# Sche1.net
KiCad netlist of a schematic drawn in EAGLE
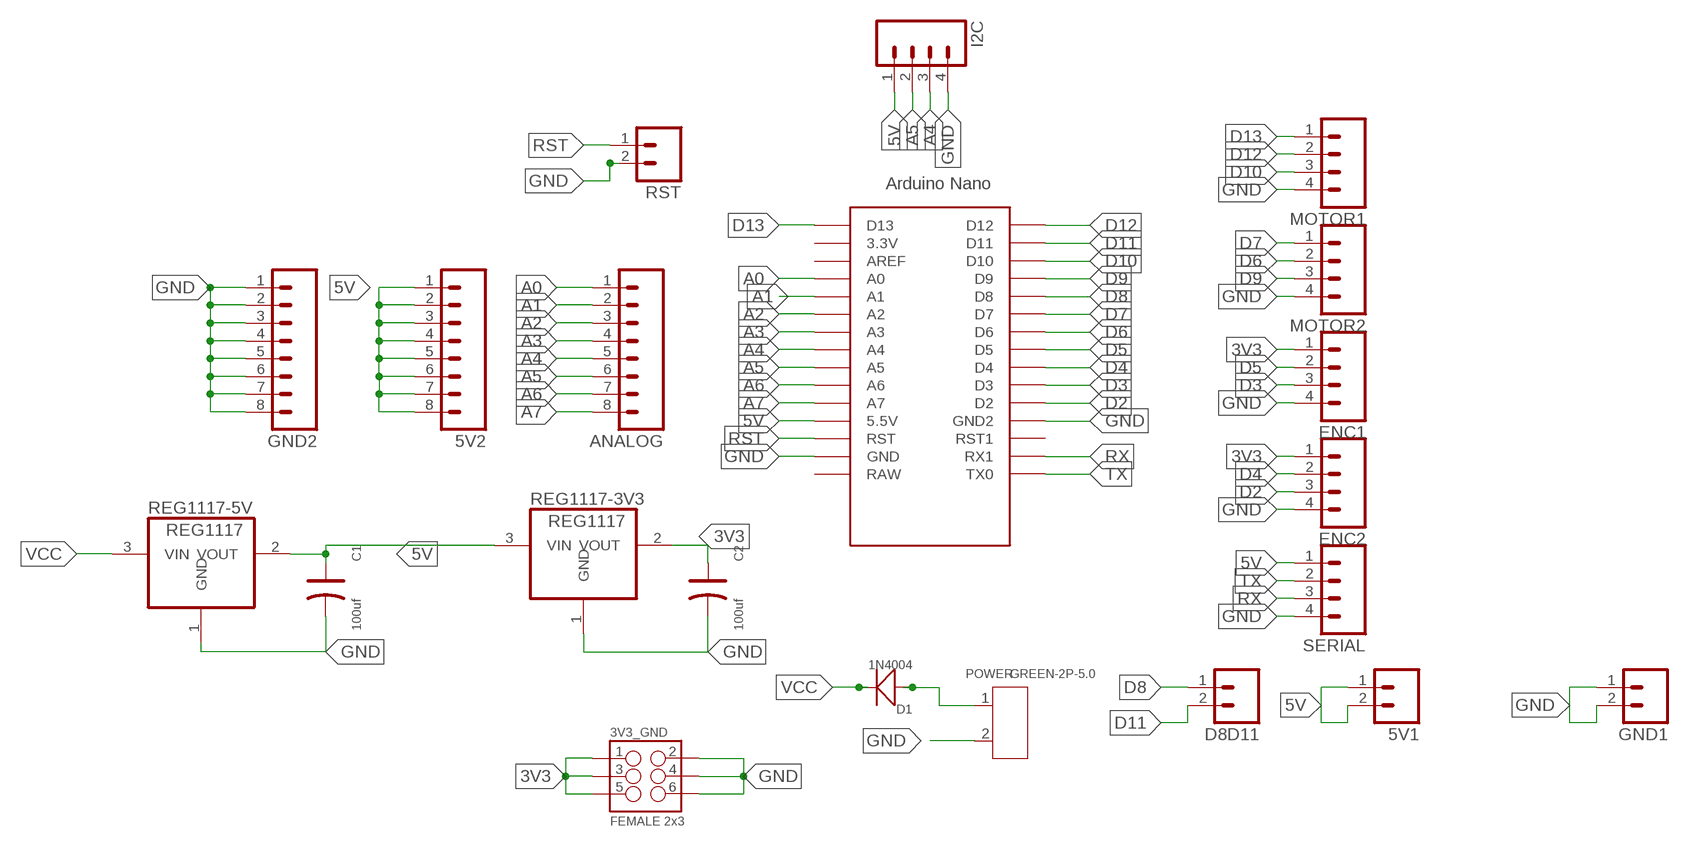
[diagram p0: schematic, sheet 1]

(export (version "E")
  (design (tool "Eeschema 10.0.6"))
  (components
    (comp (ref "3V3_GND")
      (value "FEMALE 2x3")
      (footprint "eagle-import:2X3")
      (libsource (lib "eagle-import") (part "M03X2FEMALE"))
    )
    (comp (ref "5V1")
      (value "M02PTH")
      (footprint "eagle-import:1X02")
      (libsource (lib "eagle-import") (part "M02PTH"))
    )
    (comp (ref "5V2")
      (value "M08SILK_FEMALE_PTH")
      (footprint "eagle-import:1X08")
      (libsource (lib "eagle-import") (part "M08SILK_FEMALE_PTH"))
    )
    (comp (ref "ANALOG")
      (value "M08SILK_FEMALE_PTH")
      (footprint "eagle-import:1X08")
      (libsource (lib "eagle-import") (part "M08SILK_FEMALE_PTH"))
    )
    (comp (ref "C1")
      (value "100uf")
      (footprint "eagle-import:PC-D5.3MM")
      (fields (field (name "MPN") "KS 100uF/16V"))
      (libsource (lib "eagle-import") (part "DIP-ALUMINUM-100UF-16V(D5-H7MM)"))
    )
    (comp (ref "C2")
      (value "100uf")
      (footprint "eagle-import:PC-D5.3MM")
      (fields (field (name "MPN") "KS 100uF/16V"))
      (libsource (lib "eagle-import") (part "DIP-ALUMINUM-100UF-16V(D5-H7MM)"))
    )
    (comp (ref "D1")
      (value "1N4004")
      (footprint "eagle-import:DO-41")
      (libsource (lib "eagle-import") (part "DIP-DIODE-400V-1A(DO-41)"))
    )
    (comp (ref "D8D11")
      (value "M02PTH")
      (footprint "eagle-import:1X02")
      (libsource (lib "eagle-import") (part "M02PTH"))
    )
    (comp (ref "ENC1")
      (value "M04PTH")
      (footprint "eagle-import:1X04")
      (libsource (lib "eagle-import") (part "M04PTH"))
    )
    (comp (ref "ENC2")
      (value "M04PTH")
      (footprint "eagle-import:1X04")
      (libsource (lib "eagle-import") (part "M04PTH"))
    )
    (comp (ref "GND1")
      (value "M02PTH")
      (footprint "eagle-import:1X02")
      (libsource (lib "eagle-import") (part "M02PTH"))
    )
    (comp (ref "GND2")
      (value "M08SILK_FEMALE_PTH")
      (footprint "eagle-import:1X08")
      (libsource (lib "eagle-import") (part "M08SILK_FEMALE_PTH"))
    )
    (comp (ref "I2C")
      (value "M04PTH")
      (footprint "eagle-import:1X04")
      (libsource (lib "eagle-import") (part "M04PTH"))
    )
    (comp (ref "MOTOR1")
      (value "M04PTH")
      (footprint "eagle-import:1X04")
      (libsource (lib "eagle-import") (part "M04PTH"))
    )
    (comp (ref "MOTOR2")
      (value "M04PTH")
      (footprint "eagle-import:1X04")
      (libsource (lib "eagle-import") (part "M04PTH"))
    )
    (comp (ref "POWER")
      (value "GREEN-2P-5.0")
      (footprint "eagle-import:H2-5.0-10.5X8.0MM")
      (libsource (lib "eagle-import") (part "SCREW-TERMINAL-GREEN(2P-5.0)"))
    )
    (comp (ref "REG1117-3V3")
      (value "REG1117")
      (footprint "eagle-import:SOT223")
      (libsource (lib "eagle-import") (part "REG1117"))
    )
    (comp (ref "REG1117-5V")
      (value "REG1117")
      (footprint "eagle-import:SOT223")
      (libsource (lib "eagle-import") (part "REG1117"))
    )
    (comp (ref "RST")
      (value "M02PTH")
      (footprint "eagle-import:1X02")
      (libsource (lib "eagle-import") (part "M02PTH"))
    )
    (comp (ref "SERIAL")
      (value "M04PTH")
      (footprint "eagle-import:1X04")
      (libsource (lib "eagle-import") (part "M04PTH"))
    )
    (comp (ref "U$1")
      (value "NANO")
      (footprint "eagle-import:NANO")
      (libsource (lib "eagle-import") (part "NANO"))
    )
  )
  (nets
    (net (code "1") (name "3V3") (class "Default")
      (node (ref "3V3_GND") (pin "1") (pinfunction "1_1") (pintype "bidirectional"))
      (node (ref "3V3_GND") (pin "3") (pinfunction "3_3") (pintype "bidirectional"))
      (node (ref "3V3_GND") (pin "5") (pinfunction "5_5") (pintype "bidirectional"))
      (node (ref "C2") (pin "+") (pinfunction "+_+") (pintype "passive"))
      (node (ref "ENC1") (pin "1") (pinfunction "1_1") (pintype "passive"))
      (node (ref "ENC2") (pin "1") (pinfunction "1_1") (pintype "passive"))
      (node (ref "REG1117-3V3") (pin "2") (pinfunction "VOUT_2") (pintype "output"))
    )
    (net (code "2") (name "5V") (class "Default")
      (node (ref "5V1") (pin "1") (pinfunction "1_1") (pintype "passive"))
      (node (ref "5V1") (pin "2") (pinfunction "2_2") (pintype "passive"))
      (node (ref "5V2") (pin "1") (pinfunction "1_1") (pintype "passive"))
      (node (ref "5V2") (pin "2") (pinfunction "2_2") (pintype "passive"))
      (node (ref "5V2") (pin "3") (pinfunction "3_3") (pintype "passive"))
      (node (ref "5V2") (pin "4") (pinfunction "4_4") (pintype "passive"))
      (node (ref "5V2") (pin "5") (pinfunction "5_5") (pintype "passive"))
      (node (ref "5V2") (pin "6") (pinfunction "6_6") (pintype "passive"))
      (node (ref "5V2") (pin "7") (pinfunction "7_7") (pintype "passive"))
      (node (ref "5V2") (pin "8") (pinfunction "8_8") (pintype "passive"))
      (node (ref "C1") (pin "+") (pinfunction "+_+") (pintype "passive"))
      (node (ref "I2C") (pin "1") (pinfunction "1_1") (pintype "passive"))
      (node (ref "REG1117-3V3") (pin "3") (pinfunction "VIN_3") (pintype "input"))
      (node (ref "REG1117-5V") (pin "2") (pinfunction "VOUT_2") (pintype "output"))
      (node (ref "SERIAL") (pin "1") (pinfunction "1_1") (pintype "passive"))
      (node (ref "U$1") (pin "5V") (pinfunction "5.5V_5V") (pintype "bidirectional"))
    )
    (net (code "3") (name "A0") (class "Default")
      (node (ref "ANALOG") (pin "1") (pinfunction "1_1") (pintype "passive"))
      (node (ref "U$1") (pin "A0") (pinfunction "A0_A0") (pintype "bidirectional"))
    )
    (net (code "4") (name "A1") (class "Default")
      (node (ref "ANALOG") (pin "2") (pinfunction "2_2") (pintype "passive"))
      (node (ref "U$1") (pin "A1") (pinfunction "A1_A1") (pintype "bidirectional"))
    )
    (net (code "5") (name "A2") (class "Default")
      (node (ref "ANALOG") (pin "3") (pinfunction "3_3") (pintype "passive"))
      (node (ref "U$1") (pin "A2") (pinfunction "A2_A2") (pintype "bidirectional"))
    )
    (net (code "6") (name "A3") (class "Default")
      (node (ref "ANALOG") (pin "4") (pinfunction "4_4") (pintype "passive"))
      (node (ref "U$1") (pin "A3") (pinfunction "A3_A3") (pintype "bidirectional"))
    )
    (net (code "7") (name "A4") (class "Default")
      (node (ref "ANALOG") (pin "5") (pinfunction "5_5") (pintype "passive"))
      (node (ref "I2C") (pin "3") (pinfunction "3_3") (pintype "passive"))
      (node (ref "U$1") (pin "A4") (pinfunction "A4_A4") (pintype "bidirectional"))
    )
    (net (code "8") (name "A5") (class "Default")
      (node (ref "ANALOG") (pin "6") (pinfunction "6_6") (pintype "passive"))
      (node (ref "I2C") (pin "2") (pinfunction "2_2") (pintype "passive"))
      (node (ref "U$1") (pin "A5") (pinfunction "A5_A5") (pintype "bidirectional"))
    )
    (net (code "9") (name "A6") (class "Default")
      (node (ref "ANALOG") (pin "7") (pinfunction "7_7") (pintype "passive"))
      (node (ref "U$1") (pin "A6") (pinfunction "A6_A6") (pintype "bidirectional"))
    )
    (net (code "10") (name "A7") (class "Default")
      (node (ref "ANALOG") (pin "8") (pinfunction "8_8") (pintype "passive"))
      (node (ref "U$1") (pin "A7") (pinfunction "A7_A7") (pintype "bidirectional"))
    )
    (net (code "11") (name "D2") (class "Default")
      (node (ref "ENC2") (pin "3") (pinfunction "3_3") (pintype "passive"))
      (node (ref "U$1") (pin "D2") (pinfunction "D2_D2") (pintype "bidirectional"))
    )
    (net (code "12") (name "D3") (class "Default")
      (node (ref "ENC1") (pin "3") (pinfunction "3_3") (pintype "passive"))
      (node (ref "U$1") (pin "D3") (pinfunction "D3_D3") (pintype "bidirectional"))
    )
    (net (code "13") (name "D4") (class "Default")
      (node (ref "ENC2") (pin "2") (pinfunction "2_2") (pintype "passive"))
      (node (ref "U$1") (pin "D4") (pinfunction "D4_D4") (pintype "bidirectional"))
    )
    (net (code "14") (name "D5") (class "Default")
      (node (ref "ENC1") (pin "2") (pinfunction "2_2") (pintype "passive"))
      (node (ref "U$1") (pin "D5") (pinfunction "D5_D5") (pintype "bidirectional"))
    )
    (net (code "15") (name "D6") (class "Default")
      (node (ref "MOTOR2") (pin "2") (pinfunction "2_2") (pintype "passive"))
      (node (ref "U$1") (pin "D6") (pinfunction "D6_D6") (pintype "bidirectional"))
    )
    (net (code "16") (name "D7") (class "Default")
      (node (ref "MOTOR2") (pin "1") (pinfunction "1_1") (pintype "passive"))
      (node (ref "U$1") (pin "D7") (pinfunction "D7_D7") (pintype "bidirectional"))
    )
    (net (code "17") (name "D8") (class "Default")
      (node (ref "D8D11") (pin "1") (pinfunction "1_1") (pintype "passive"))
      (node (ref "U$1") (pin "D8") (pinfunction "D8_D8") (pintype "bidirectional"))
    )
    (net (code "18") (name "D9") (class "Default")
      (node (ref "MOTOR2") (pin "3") (pinfunction "3_3") (pintype "passive"))
      (node (ref "U$1") (pin "D9") (pinfunction "D9_D9") (pintype "bidirectional"))
    )
    (net (code "19") (name "D10") (class "Default")
      (node (ref "MOTOR1") (pin "3") (pinfunction "3_3") (pintype "passive"))
      (node (ref "U$1") (pin "D10") (pinfunction "D10_D10") (pintype "bidirectional"))
    )
    (net (code "20") (name "D11") (class "Default")
      (node (ref "D8D11") (pin "2") (pinfunction "2_2") (pintype "passive"))
      (node (ref "U$1") (pin "D11") (pinfunction "D11_D11") (pintype "bidirectional"))
    )
    (net (code "21") (name "D12") (class "Default")
      (node (ref "MOTOR1") (pin "2") (pinfunction "2_2") (pintype "passive"))
      (node (ref "U$1") (pin "D12") (pinfunction "D12_D12") (pintype "bidirectional"))
    )
    (net (code "22") (name "D13") (class "Default")
      (node (ref "MOTOR1") (pin "1") (pinfunction "1_1") (pintype "passive"))
      (node (ref "U$1") (pin "D13") (pinfunction "D13_D13") (pintype "bidirectional"))
    )
    (net (code "23") (name "GND") (class "Default")
      (node (ref "3V3_GND") (pin "2") (pinfunction "2_2") (pintype "bidirectional"))
      (node (ref "3V3_GND") (pin "4") (pinfunction "4_4") (pintype "bidirectional"))
      (node (ref "3V3_GND") (pin "6") (pinfunction "6_6") (pintype "bidirectional"))
      (node (ref "C1") (pin "-") (pinfunction "-_-") (pintype "passive"))
      (node (ref "C2") (pin "-") (pinfunction "-_-") (pintype "passive"))
      (node (ref "ENC1") (pin "4") (pinfunction "4_4") (pintype "passive"))
      (node (ref "ENC2") (pin "4") (pinfunction "4_4") (pintype "passive"))
      (node (ref "GND1") (pin "1") (pinfunction "1_1") (pintype "passive"))
      (node (ref "GND1") (pin "2") (pinfunction "2_2") (pintype "passive"))
      (node (ref "GND2") (pin "1") (pinfunction "1_1") (pintype "passive"))
      (node (ref "GND2") (pin "2") (pinfunction "2_2") (pintype "passive"))
      (node (ref "GND2") (pin "3") (pinfunction "3_3") (pintype "passive"))
      (node (ref "GND2") (pin "4") (pinfunction "4_4") (pintype "passive"))
      (node (ref "GND2") (pin "5") (pinfunction "5_5") (pintype "passive"))
      (node (ref "GND2") (pin "6") (pinfunction "6_6") (pintype "passive"))
      (node (ref "GND2") (pin "7") (pinfunction "7_7") (pintype "passive"))
      (node (ref "GND2") (pin "8") (pinfunction "8_8") (pintype "passive"))
      (node (ref "I2C") (pin "4") (pinfunction "4_4") (pintype "passive"))
      (node (ref "MOTOR1") (pin "4") (pinfunction "4_4") (pintype "passive"))
      (node (ref "MOTOR2") (pin "4") (pinfunction "4_4") (pintype "passive"))
      (node (ref "POWER") (pin "2") (pinfunction "2_2") (pintype "bidirectional"))
      (node (ref "REG1117-3V3") (pin "1") (pinfunction "GND_1") (pintype "power_in"))
      (node (ref "REG1117-5V") (pin "1") (pinfunction "GND_1") (pintype "power_in"))
      (node (ref "RST") (pin "2") (pinfunction "2_2") (pintype "passive"))
      (node (ref "SERIAL") (pin "4") (pinfunction "4_4") (pintype "passive"))
      (node (ref "U$1") (pin "GND") (pinfunction "GND_GND") (pintype "bidirectional"))
      (node (ref "U$1") (pin "GND1") (pinfunction "GND2_GND1") (pintype "bidirectional"))
    )
    (net (code "24") (name "Net-(D1-+)") (class "Default")
      (node (ref "D1") (pin "1") (pinfunction "+_1") (pintype "passive"))
      (node (ref "POWER") (pin "1") (pinfunction "1_1") (pintype "bidirectional"))
    )
    (net (code "25") (name "RST") (class "Default")
      (node (ref "RST") (pin "1") (pinfunction "1_1") (pintype "passive"))
      (node (ref "U$1") (pin "RST") (pinfunction "RST_RST") (pintype "bidirectional"))
    )
    (net (code "26") (name "RX") (class "Default")
      (node (ref "SERIAL") (pin "3") (pinfunction "3_3") (pintype "passive"))
      (node (ref "U$1") (pin "RX1") (pinfunction "RX1_RX1") (pintype "bidirectional"))
    )
    (net (code "27") (name "TX") (class "Default")
      (node (ref "SERIAL") (pin "2") (pinfunction "2_2") (pintype "passive"))
      (node (ref "U$1") (pin "TX0") (pinfunction "TX0_TX0") (pintype "bidirectional"))
    )
    (net (code "28") (name "VCC") (class "Default")
      (node (ref "D1") (pin "2") (pinfunction "-_2") (pintype "passive"))
      (node (ref "REG1117-5V") (pin "3") (pinfunction "VIN_3") (pintype "input"))
    )
    (net (code "29") (name "unconnected-(U$1-Pad3.3V)") (class "Default")
      (node (ref "U$1") (pin "3.3V") (pinfunction "3.3V_3.3V") (pintype "bidirectional"))
    )
    (net (code "30") (name "unconnected-(U$1-PadAREF)") (class "Default")
      (node (ref "U$1") (pin "AREF") (pinfunction "AREF_AREF") (pintype "bidirectional"))
    )
    (net (code "31") (name "unconnected-(U$1-PadRAW)") (class "Default")
      (node (ref "U$1") (pin "RAW") (pinfunction "RAW_RAW") (pintype "bidirectional"))
    )
    (net (code "32") (name "unconnected-(U$1-PadRST1)") (class "Default")
      (node (ref "U$1") (pin "RST1") (pinfunction "RST1_RST1") (pintype "bidirectional"))
    )
  )
)
